# ADC.net
KiCad netlist of a schematic drawn in Altium Designer
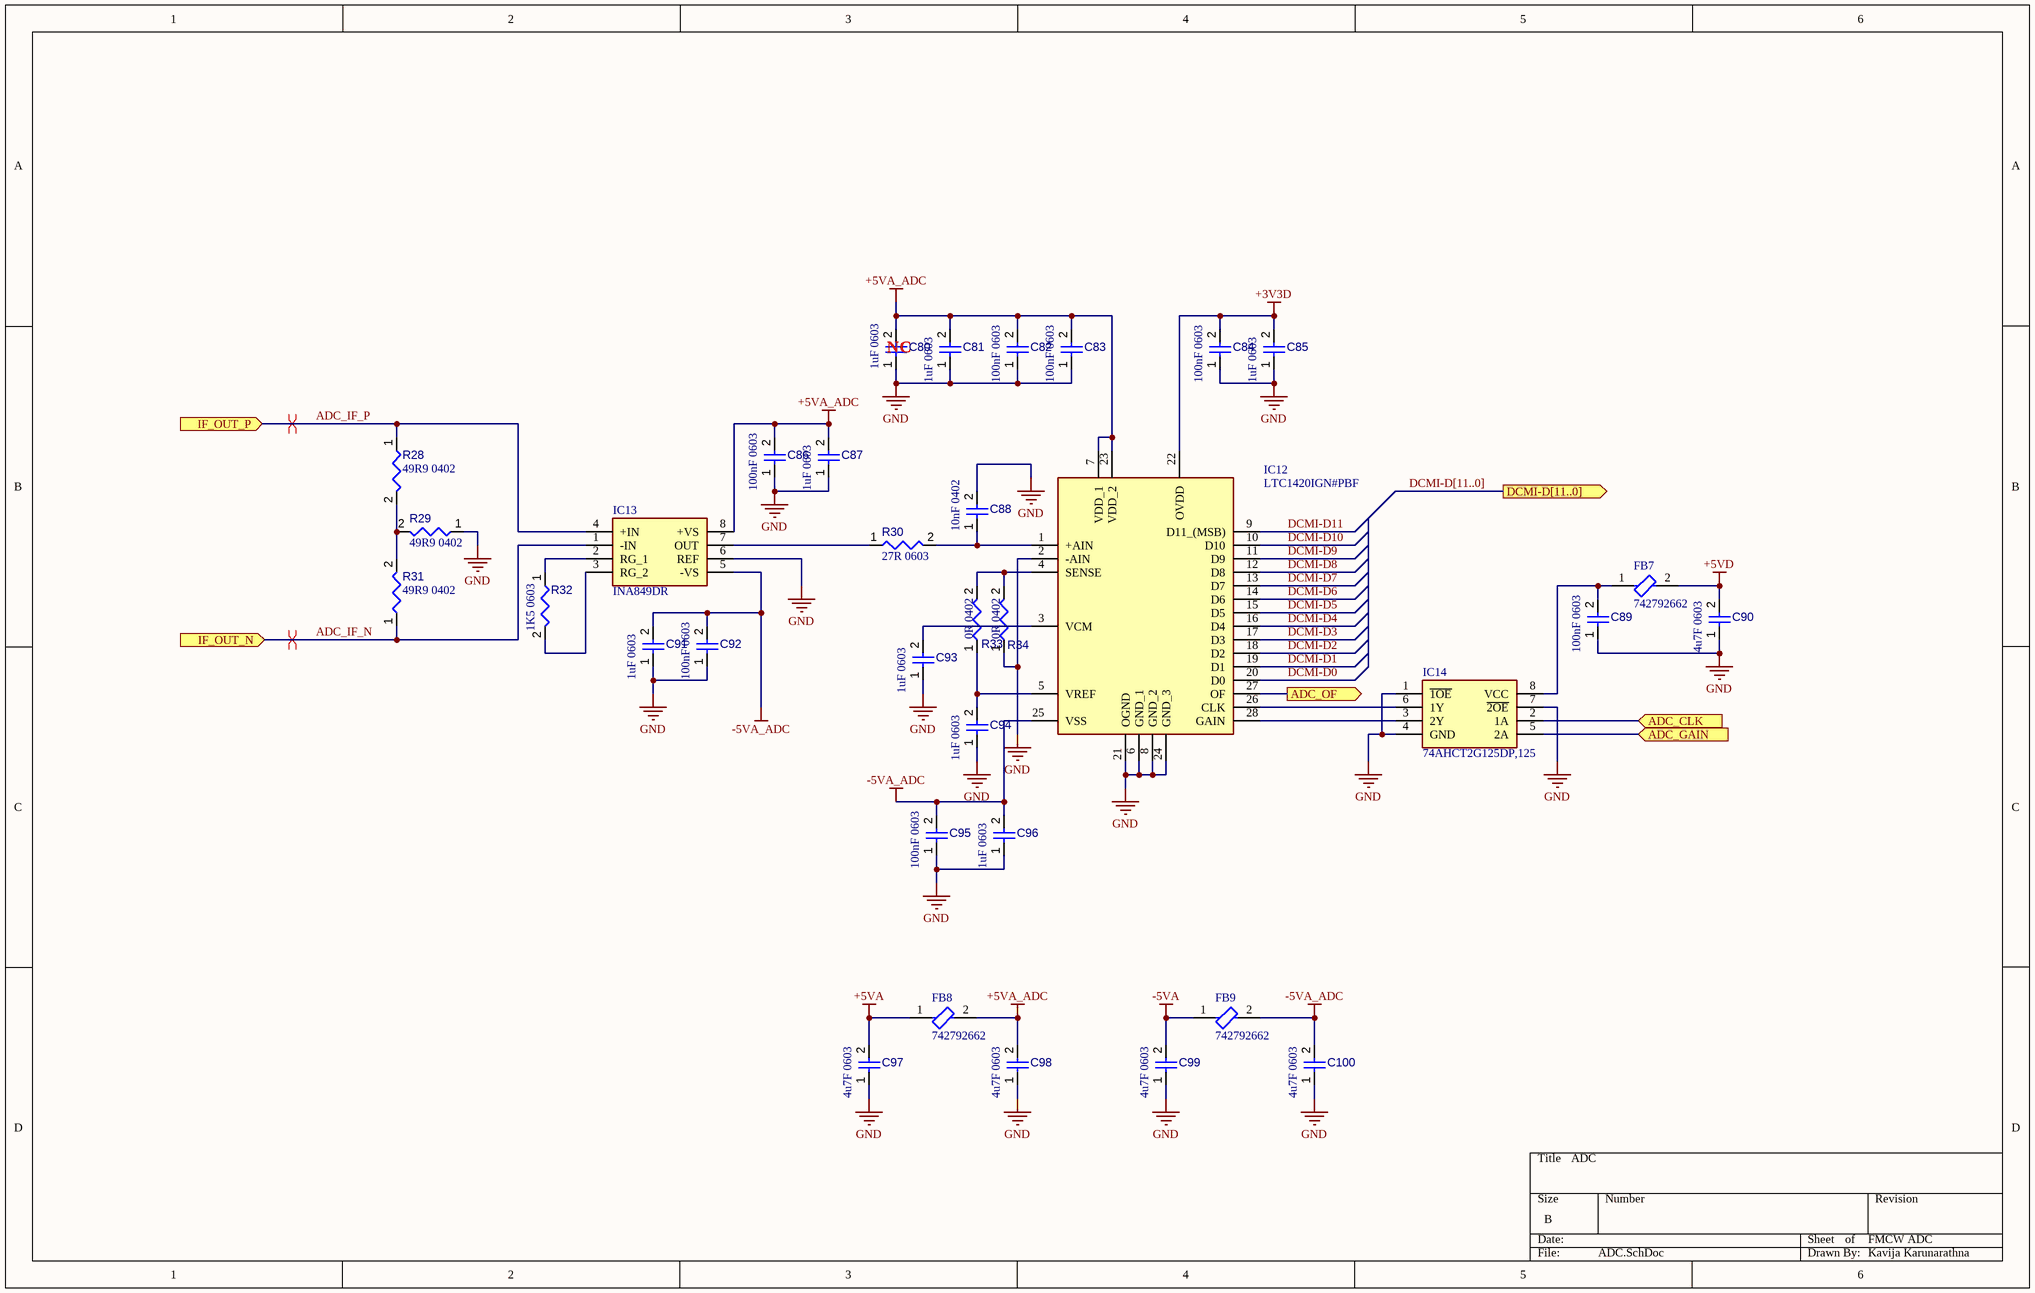
[diagram p0: ADC.SchDoc]

(export (version "E")
  (design (tool "Eeschema 10.0.6"))
  (components
    (comp (ref "C80")
      (value "1uF 0603")
      (footprint "CAPC0603(1608)100_L")
      (description "Chip Capacitor, 1µF +/-0.1%, 25V, 0603, Thickness 1 mm")
      (fields (field (name "TOLERANCE") "20%") (field (name "MANUFACTURER PART NO") "0603YC105KAZ2A"))
      (libsource (lib "Kavija Karunarathna") (part "CAP-NP-2"))
    )
    (comp (ref "C81")
      (value "1uF 0603")
      (footprint "CAPC0603(1608)100_L")
      (description "Chip Capacitor, 1µF +/-0.1%, 25V, 0603, Thickness 1 mm")
      (fields (field (name "TOLERANCE") "20%") (field (name "MANUFACTURER PART NO") "0603YC105KAZ2A"))
      (libsource (lib "Kavija Karunarathna") (part "CAP-NP-2"))
    )
    (comp (ref "C82")
      (value "100nF 0603")
      (footprint "CAPC0603(1608)100_L")
      (description "Chip Capacitor, 1µF +/-0.1%, 25V, 0603, Thickness 1 mm")
      (fields (field (name "TOLERANCE") "20%") (field (name "MANUFACTURER PART NO") "0603X104K250CT"))
      (libsource (lib "Kavija Karunarathna") (part "CAP-NP-2"))
    )
    (comp (ref "C83")
      (value "100nF 0603")
      (footprint "CAPC0603(1608)100_L")
      (description "Chip Capacitor, 1µF +/-0.1%, 25V, 0603, Thickness 1 mm")
      (fields (field (name "TOLERANCE") "20%") (field (name "MANUFACTURER PART NO") "0603X104K250CT"))
      (libsource (lib "Kavija Karunarathna") (part "CAP-NP-2"))
    )
    (comp (ref "C84")
      (value "100nF 0603")
      (footprint "CAPC0603(1608)100_L")
      (description "Chip Capacitor, 1µF +/-0.1%, 25V, 0603, Thickness 1 mm")
      (fields (field (name "TOLERANCE") "20%") (field (name "MANUFACTURER PART NO") "0603X104K250CT"))
      (libsource (lib "Kavija Karunarathna") (part "CAP-NP-2"))
    )
    (comp (ref "C85")
      (value "1uF 0603")
      (footprint "CAPC0603(1608)100_L")
      (description "Chip Capacitor, 1µF +/-0.1%, 25V, 0603, Thickness 1 mm")
      (fields (field (name "TOLERANCE") "20%") (field (name "MANUFACTURER PART NO") "0603YC105KAZ2A"))
      (libsource (lib "Kavija Karunarathna") (part "CAP-NP-2"))
    )
    (comp (ref "C86")
      (value "100nF 0603")
      (footprint "CAPC0603(1608)100_L")
      (description "Chip Capacitor, 1µF +/-0.1%, 25V, 0603, Thickness 1 mm")
      (fields (field (name "TOLERANCE") "20%") (field (name "MANUFACTURER PART NO") "0603X104K250CT"))
      (libsource (lib "Kavija Karunarathna") (part "CAP-NP-2"))
    )
    (comp (ref "C87")
      (value "1uF 0603")
      (footprint "CAPC0603(1608)100_L")
      (description "Chip Capacitor, 1µF +/-0.1%, 25V, 0603, Thickness 1 mm")
      (fields (field (name "TOLERANCE") "20%") (field (name "MANUFACTURER PART NO") "0603YC105KAZ2A"))
      (libsource (lib "Kavija Karunarathna") (part "CAP-NP-2"))
    )
    (comp (ref "C88")
      (value "10nF 0402")
      (footprint "CAPC0402(1005)60_L")
      (description "Multilayer Ceramic Capacitors MLCC - SMD/SMT 50 V 10 pF C0G 0402 1%")
      (fields (field (name "TOLERANCE") "20%") (field (name "MANUFACTURER PART NO") "VJ0402Y103JXJAC"))
      (libsource (lib "Kavija Karunarathna") (part "CAP-NP-2"))
    )
    (comp (ref "C89")
      (value "100nF 0603")
      (footprint "CAPC0603(1608)100_L")
      (description "Chip Capacitor, 1µF +/-0.1%, 25V, 0603, Thickness 1 mm")
      (fields (field (name "TOLERANCE") "20%") (field (name "MANUFACTURER PART NO") "0603X104K250CT"))
      (libsource (lib "Kavija Karunarathna") (part "CAP-NP-2"))
    )
    (comp (ref "C90")
      (value "4u7F 0603")
      (footprint "CAPC0603(1608)100_L")
      (description "Chip Capacitor, 1µF +/-0.1%, 25V, 0603, Thickness 1 mm")
      (fields (field (name "TOLERANCE") "20%") (field (name "MANUFACTURER PART NO") "06033D475KAT2A"))
      (libsource (lib "Kavija Karunarathna") (part "CAP-NP-2"))
    )
    (comp (ref "C91")
      (value "1uF 0603")
      (footprint "CAPC0603(1608)100_L")
      (description "Chip Capacitor, 1µF +/-0.1%, 25V, 0603, Thickness 1 mm")
      (fields (field (name "TOLERANCE") "20%") (field (name "MANUFACTURER PART NO") "0603YC105KAZ2A"))
      (libsource (lib "Kavija Karunarathna") (part "CAP-NP-2"))
    )
    (comp (ref "C92")
      (value "100nF 0603")
      (footprint "CAPC0603(1608)100_L")
      (description "Chip Capacitor, 1µF +/-0.1%, 25V, 0603, Thickness 1 mm")
      (fields (field (name "TOLERANCE") "20%") (field (name "MANUFACTURER PART NO") "0603X104K250CT"))
      (libsource (lib "Kavija Karunarathna") (part "CAP-NP-2"))
    )
    (comp (ref "C93")
      (value "1uF 0603")
      (footprint "CAPC0603(1608)100_L")
      (description "Chip Capacitor, 1µF +/-0.1%, 25V, 0603, Thickness 1 mm")
      (fields (field (name "TOLERANCE") "20%") (field (name "MANUFACTURER PART NO") "0603YC105KAZ2A"))
      (libsource (lib "Kavija Karunarathna") (part "CAP-NP-2"))
    )
    (comp (ref "C94")
      (value "1uF 0603")
      (footprint "CAPC0603(1608)100_L")
      (description "Chip Capacitor, 1µF +/-0.1%, 25V, 0603, Thickness 1 mm")
      (fields (field (name "TOLERANCE") "20%") (field (name "MANUFACTURER PART NO") "0603YC105KAZ2A"))
      (libsource (lib "Kavija Karunarathna") (part "CAP-NP-2"))
    )
    (comp (ref "C95")
      (value "100nF 0603")
      (footprint "CAPC0603(1608)100_L")
      (description "Chip Capacitor, 1µF +/-0.1%, 25V, 0603, Thickness 1 mm")
      (fields (field (name "TOLERANCE") "20%") (field (name "MANUFACTURER PART NO") "0603X104K250CT"))
      (libsource (lib "Kavija Karunarathna") (part "CAP-NP-2"))
    )
    (comp (ref "C96")
      (value "1uF 0603")
      (footprint "CAPC0603(1608)100_L")
      (description "Chip Capacitor, 1µF +/-0.1%, 25V, 0603, Thickness 1 mm")
      (fields (field (name "TOLERANCE") "20%") (field (name "MANUFACTURER PART NO") "0603YC105KAZ2A"))
      (libsource (lib "Kavija Karunarathna") (part "CAP-NP-2"))
    )
    (comp (ref "C97")
      (value "4u7F 0603")
      (footprint "CAPC0603(1608)100_L")
      (description "Chip Capacitor, 1µF +/-0.1%, 25V, 0603, Thickness 1 mm")
      (fields (field (name "TOLERANCE") "20%") (field (name "MANUFACTURER PART NO") "06033D475KAT2A"))
      (libsource (lib "Kavija Karunarathna") (part "CAP-NP-2"))
    )
    (comp (ref "C98")
      (value "4u7F 0603")
      (footprint "CAPC0603(1608)100_L")
      (description "Chip Capacitor, 1µF +/-0.1%, 25V, 0603, Thickness 1 mm")
      (fields (field (name "TOLERANCE") "20%") (field (name "MANUFACTURER PART NO") "06033D475KAT2A"))
      (libsource (lib "Kavija Karunarathna") (part "CAP-NP-2"))
    )
    (comp (ref "C99")
      (value "4u7F 0603")
      (footprint "CAPC0603(1608)100_L")
      (description "Chip Capacitor, 1µF +/-0.1%, 25V, 0603, Thickness 1 mm")
      (fields (field (name "TOLERANCE") "20%") (field (name "MANUFACTURER PART NO") "06033D475KAT2A"))
      (libsource (lib "Kavija Karunarathna") (part "CAP-NP-2"))
    )
    (comp (ref "C100")
      (value "4u7F 0603")
      (footprint "CAPC0603(1608)100_L")
      (description "Chip Capacitor, 1µF +/-0.1%, 25V, 0603, Thickness 1 mm")
      (fields (field (name "TOLERANCE") "20%") (field (name "MANUFACTURER PART NO") "06033D475KAT2A"))
      (libsource (lib "Kavija Karunarathna") (part "CAP-NP-2"))
    )
    (comp (ref "FB7")
      (value "742792662")
      (footprint "FB-0603")
      (description "FERRITE BEAD 0603")
      (fields (field (name "MOUSER PART NO") "710-742792662"))
      (libsource (lib "SchLib") (part "742792662-FB"))
    )
    (comp (ref "FB8")
      (value "742792662")
      (footprint "FB-0603")
      (description "FERRITE BEAD 0603")
      (fields (field (name "MOUSER PART NO") "710-742792662"))
      (libsource (lib "SchLib") (part "742792662-FB"))
    )
    (comp (ref "FB9")
      (value "742792662")
      (footprint "FB-0603")
      (description "FERRITE BEAD 0603")
      (fields (field (name "MOUSER PART NO") "710-742792662"))
      (libsource (lib "SchLib") (part "742792662-FB"))
    )
    (comp (ref "IC12")
      (value "LTC1420IGN#PBF")
      (footprint "SOP64P601X175-28N")
      (description "Integrated Circuit")
      (fields (field (name "MOUSER PART NO") "584-LTC1420IGN#PBF"))
      (libsource (lib "SchLib") (part "LTC1420IGN#PBF"))
    )
    (comp (ref "IC13")
      (value "INA849DR")
      (footprint "SOIC127P600X175-8N")
      (description "Integrated Circuit")
      (fields (field (name "MOUSER PART NO") "595-INA849DR"))
      (libsource (lib "SchLib") (part "INA849DR"))
    )
    (comp (ref "IC14")
      (value "74AHCT2G125DP,125")
      (footprint "SOP65P400X110-8N")
      (description "Integrated Circuit")
      (fields (field (name "MOUSER PART NO") "771-AHCT2G125DP125"))
      (libsource (lib "SchLib") (part "74AHCT2G125DP,125"))
    )
    (comp (ref "R28")
      (value "49R9 0402")
      (footprint "RESC0402(1005)_L")
      (description "Thin Film Resistors - SMD 49.9 OHM .1% 50PPM 1/16W")
      (fields (field (name "TOLERANCE") "1%") (field (name "POWER") "100mW"))
      (libsource (lib "Kavija Karunarathna") (part "383KR2F"))
    )
    (comp (ref "R29")
      (value "49R9 0402")
      (footprint "RESC0402(1005)_L")
      (description "Thin Film Resistors - SMD 49.9 OHM .1% 50PPM 1/16W")
      (fields (field (name "TOLERANCE") "1%") (field (name "POWER") "100mW"))
      (libsource (lib "Kavija Karunarathna") (part "383KR2F"))
    )
    (comp (ref "R30")
      (value "27R 0603")
      (footprint "RESC0603(1608)_L")
      (description "Thick Film Resistors - SMD General Purpose Chip Resistor 0603, 200Ohms, 1%, 1/10W")
      (fields (field (name "POWER") "100mW") (field (name "TOLERANCE") "5%"))
      (libsource (lib "Kavija Karunarathna") (part "120R3J"))
    )
    (comp (ref "R31")
      (value "49R9 0402")
      (footprint "RESC0402(1005)_L")
      (description "Thin Film Resistors - SMD 49.9 OHM .1% 50PPM 1/16W")
      (fields (field (name "TOLERANCE") "1%") (field (name "POWER") "100mW"))
      (libsource (lib "Kavija Karunarathna") (part "383KR2F"))
    )
    (comp (ref "R32")
      (value "1K5 0603")
      (footprint "RESC0603(1608)_L")
      (description "Thick Film Resistors - SMD WRIS-RSKS 100 Ohms 1 % 0.1 W 0603 AEC-Q200")
      (fields (field (name "POWER") "100mW") (field (name "TOLERANCE") "5%"))
      (libsource (lib "Kavija Karunarathna") (part "120R3J"))
    )
    (comp (ref "R33")
      (value "0R 0402")
      (footprint "RESC0402(1005)_L")
      (description "Thick Film Resistors - SMD 0 Ohms 1/16 W 50 V 5 % 0402 - 55 C / + 155 C AEC-Q200")
      (fields (field (name "TOLERANCE") "1%") (field (name "POWER") "100mW"))
      (libsource (lib "Kavija Karunarathna") (part "383KR2F"))
    )
    (comp (ref "R34")
      (value "0R 0402")
      (footprint "RESC0402(1005)_L")
      (description "Thick Film Resistors - SMD 0 Ohms 1/16 W 50 V 5 % 0402 - 55 C / + 155 C AEC-Q200")
      (fields (field (name "TOLERANCE") "1%") (field (name "POWER") "100mW"))
      (libsource (lib "Kavija Karunarathna") (part "383KR2F"))
    )
  )
  (nets
    (net (code "1") (name "+3V3D") (class "Default")
      (node (ref "C84") (pin "2") (pinfunction "2_2") (pintype "passive"))
      (node (ref "C85") (pin "2") (pinfunction "2_2") (pintype "passive"))
      (node (ref "IC12") (pin "22") (pinfunction "OVDD_22") (pintype "passive"))
    )
    (net (code "2") (name "+5VA") (class "Default")
      (node (ref "C97") (pin "2") (pinfunction "2_2") (pintype "passive"))
      (node (ref "FB8") (pin "1") (pinfunction "1_1") (pintype "passive"))
    )
    (net (code "3") (name "+5VA_ADC") (class "Default")
      (node (ref "C80") (pin "2") (pinfunction "2_2") (pintype "passive"))
      (node (ref "C81") (pin "2") (pinfunction "2_2") (pintype "passive"))
      (node (ref "C82") (pin "2") (pinfunction "2_2") (pintype "passive"))
      (node (ref "C83") (pin "2") (pinfunction "2_2") (pintype "passive"))
      (node (ref "C86") (pin "2") (pinfunction "2_2") (pintype "passive"))
      (node (ref "C87") (pin "2") (pinfunction "2_2") (pintype "passive"))
      (node (ref "C98") (pin "2") (pinfunction "2_2") (pintype "passive"))
      (node (ref "FB8") (pin "2") (pinfunction "2_2") (pintype "passive"))
      (node (ref "IC12") (pin "23") (pinfunction "VDD_2_23") (pintype "passive"))
      (node (ref "IC12") (pin "7") (pinfunction "VDD_1_7") (pintype "passive"))
      (node (ref "IC13") (pin "8") (pinfunction "+VS_8") (pintype "passive"))
    )
    (net (code "4") (name "+5VD") (class "Default")
      (node (ref "C90") (pin "2") (pinfunction "2_2") (pintype "passive"))
      (node (ref "FB7") (pin "2") (pinfunction "2_2") (pintype "passive"))
    )
    (net (code "5") (name "-5VA") (class "Default")
      (node (ref "C99") (pin "2") (pinfunction "2_2") (pintype "passive"))
      (node (ref "FB9") (pin "1") (pinfunction "1_1") (pintype "passive"))
    )
    (net (code "6") (name "-5VA_ADC") (class "Default")
      (node (ref "C100") (pin "2") (pinfunction "2_2") (pintype "passive"))
      (node (ref "C91") (pin "2") (pinfunction "2_2") (pintype "passive"))
      (node (ref "C92") (pin "2") (pinfunction "2_2") (pintype "passive"))
      (node (ref "C95") (pin "2") (pinfunction "2_2") (pintype "passive"))
      (node (ref "C96") (pin "2") (pinfunction "2_2") (pintype "passive"))
      (node (ref "FB9") (pin "2") (pinfunction "2_2") (pintype "passive"))
      (node (ref "IC12") (pin "25") (pinfunction "VSS_25") (pintype "passive"))
      (node (ref "IC13") (pin "5") (pinfunction "-VS_5") (pintype "passive"))
    )
    (net (code "7") (name "/ADC_CLK") (class "Default")
      (node (ref "IC14") (pin "2") (pinfunction "1A_2") (pintype "passive"))
    )
    (net (code "8") (name "/ADC_GAIN") (class "Default")
      (node (ref "IC14") (pin "5") (pinfunction "2A_5") (pintype "passive"))
    )
    (net (code "9") (name "/ADC_IF_N") (class "Default")
      (node (ref "IC13") (pin "1") (pinfunction "-IN_1") (pintype "passive"))
      (node (ref "R31") (pin "1") (pinfunction "1_1") (pintype "passive"))
    )
    (net (code "10") (name "/ADC_IF_P") (class "Default")
      (node (ref "IC13") (pin "4") (pinfunction "+IN_4") (pintype "passive"))
      (node (ref "R28") (pin "1") (pinfunction "1_1") (pintype "passive"))
    )
    (net (code "11") (name "/ADC_OF") (class "Default")
      (node (ref "IC12") (pin "27") (pinfunction "OF_27") (pintype "passive"))
    )
    (net (code "12") (name "/DCMI-D0") (class "Default")
      (node (ref "IC12") (pin "20") (pinfunction "D0_20") (pintype "passive"))
    )
    (net (code "13") (name "/DCMI-D1") (class "Default")
      (node (ref "IC12") (pin "19") (pinfunction "D1_19") (pintype "passive"))
    )
    (net (code "14") (name "/DCMI-D2") (class "Default")
      (node (ref "IC12") (pin "18") (pinfunction "D2_18") (pintype "passive"))
    )
    (net (code "15") (name "/DCMI-D3") (class "Default")
      (node (ref "IC12") (pin "17") (pinfunction "D3_17") (pintype "passive"))
    )
    (net (code "16") (name "/DCMI-D4") (class "Default")
      (node (ref "IC12") (pin "16") (pinfunction "D4_16") (pintype "passive"))
    )
    (net (code "17") (name "/DCMI-D5") (class "Default")
      (node (ref "IC12") (pin "15") (pinfunction "D5_15") (pintype "passive"))
    )
    (net (code "18") (name "/DCMI-D6") (class "Default")
      (node (ref "IC12") (pin "14") (pinfunction "D6_14") (pintype "passive"))
    )
    (net (code "19") (name "/DCMI-D7") (class "Default")
      (node (ref "IC12") (pin "13") (pinfunction "D7_13") (pintype "passive"))
    )
    (net (code "20") (name "/DCMI-D8") (class "Default")
      (node (ref "IC12") (pin "12") (pinfunction "D8_12") (pintype "passive"))
    )
    (net (code "21") (name "/DCMI-D9") (class "Default")
      (node (ref "IC12") (pin "11") (pinfunction "D9_11") (pintype "passive"))
    )
    (net (code "22") (name "/DCMI-D10") (class "Default")
      (node (ref "IC12") (pin "10") (pinfunction "D10_10") (pintype "passive"))
    )
    (net (code "23") (name "/DCMI-D11") (class "Default")
      (node (ref "IC12") (pin "9") (pinfunction "D11_(MSB)_9") (pintype "passive"))
    )
    (net (code "25") (name "GND") (class "Default")
      (node (ref "C100") (pin "1") (pinfunction "1_1") (pintype "passive"))
      (node (ref "C80") (pin "1") (pinfunction "1_1") (pintype "passive"))
      (node (ref "C81") (pin "1") (pinfunction "1_1") (pintype "passive"))
      (node (ref "C82") (pin "1") (pinfunction "1_1") (pintype "passive"))
      (node (ref "C83") (pin "1") (pinfunction "1_1") (pintype "passive"))
      (node (ref "C84") (pin "1") (pinfunction "1_1") (pintype "passive"))
      (node (ref "C85") (pin "1") (pinfunction "1_1") (pintype "passive"))
      (node (ref "C86") (pin "1") (pinfunction "1_1") (pintype "passive"))
      (node (ref "C87") (pin "1") (pinfunction "1_1") (pintype "passive"))
      (node (ref "C88") (pin "2") (pinfunction "2_2") (pintype "passive"))
      (node (ref "C89") (pin "1") (pinfunction "1_1") (pintype "passive"))
      (node (ref "C90") (pin "1") (pinfunction "1_1") (pintype "passive"))
      (node (ref "C91") (pin "1") (pinfunction "1_1") (pintype "passive"))
      (node (ref "C92") (pin "1") (pinfunction "1_1") (pintype "passive"))
      (node (ref "C93") (pin "1") (pinfunction "1_1") (pintype "passive"))
      (node (ref "C94") (pin "1") (pinfunction "1_1") (pintype "passive"))
      (node (ref "C95") (pin "1") (pinfunction "1_1") (pintype "passive"))
      (node (ref "C96") (pin "1") (pinfunction "1_1") (pintype "passive"))
      (node (ref "C97") (pin "1") (pinfunction "1_1") (pintype "passive"))
      (node (ref "C98") (pin "1") (pinfunction "1_1") (pintype "passive"))
      (node (ref "C99") (pin "1") (pinfunction "1_1") (pintype "passive"))
      (node (ref "IC12") (pin "2") (pinfunction "-AIN_2") (pintype "passive"))
      (node (ref "IC12") (pin "21") (pinfunction "OGND_21") (pintype "passive"))
      (node (ref "IC12") (pin "24") (pinfunction "GND_3_24") (pintype "passive"))
      (node (ref "IC12") (pin "6") (pinfunction "GND_1_6") (pintype "passive"))
      (node (ref "IC12") (pin "8") (pinfunction "GND_2_8") (pintype "passive"))
      (node (ref "IC13") (pin "6") (pinfunction "REF_6") (pintype "passive"))
      (node (ref "IC14") (pin "1") (pinfunction "~{1OE}_1") (pintype "passive"))
      (node (ref "IC14") (pin "4") (pinfunction "GND_4") (pintype "passive"))
      (node (ref "IC14") (pin "7") (pinfunction "~{2OE}_7") (pintype "passive"))
      (node (ref "R29") (pin "1") (pinfunction "1_1") (pintype "passive"))
      (node (ref "R34") (pin "1") (pinfunction "1_1") (pintype "passive"))
    )
    (net (code "26") (name "Net-(IC12-+AIN)") (class "Default")
      (node (ref "C88") (pin "1") (pinfunction "1_1") (pintype "passive"))
      (node (ref "IC12") (pin "1") (pinfunction "+AIN_1") (pintype "passive"))
      (node (ref "R30") (pin "2") (pinfunction "2_2") (pintype "passive"))
    )
    (net (code "27") (name "Net-(IC12-CLK)") (class "Default")
      (node (ref "IC12") (pin "26") (pinfunction "CLK_26") (pintype "passive"))
      (node (ref "IC14") (pin "6") (pinfunction "1Y_6") (pintype "passive"))
    )
    (net (code "28") (name "Net-(IC12-GAIN)") (class "Default")
      (node (ref "IC12") (pin "28") (pinfunction "GAIN_28") (pintype "passive"))
      (node (ref "IC14") (pin "3") (pinfunction "2Y_3") (pintype "passive"))
    )
    (net (code "29") (name "Net-(IC12-SENSE)") (class "Default")
      (node (ref "IC12") (pin "4") (pinfunction "SENSE_4") (pintype "passive"))
      (node (ref "R33") (pin "2") (pinfunction "2_2") (pintype "passive"))
      (node (ref "R34") (pin "2") (pinfunction "2_2") (pintype "passive"))
    )
    (net (code "30") (name "Net-(IC12-VCM)") (class "Default")
      (node (ref "C93") (pin "2") (pinfunction "2_2") (pintype "passive"))
      (node (ref "IC12") (pin "3") (pinfunction "VCM_3") (pintype "passive"))
    )
    (net (code "31") (name "Net-(IC12-VREF)") (class "Default")
      (node (ref "C94") (pin "2") (pinfunction "2_2") (pintype "passive"))
      (node (ref "IC12") (pin "5") (pinfunction "VREF_5") (pintype "passive"))
      (node (ref "R33") (pin "1") (pinfunction "1_1") (pintype "passive"))
    )
    (net (code "32") (name "Net-(IC13-OUT)") (class "Default")
      (node (ref "IC13") (pin "7") (pinfunction "OUT_7") (pintype "passive"))
      (node (ref "R30") (pin "1") (pinfunction "1_1") (pintype "passive"))
    )
    (net (code "33") (name "Net-(IC13-RG_1)") (class "Default")
      (node (ref "IC13") (pin "2") (pinfunction "RG_1_2") (pintype "passive"))
      (node (ref "R32") (pin "1") (pinfunction "1_1") (pintype "passive"))
    )
    (net (code "34") (name "Net-(IC13-RG_2)") (class "Default")
      (node (ref "IC13") (pin "3") (pinfunction "RG_2_3") (pintype "passive"))
      (node (ref "R32") (pin "2") (pinfunction "2_2") (pintype "passive"))
    )
    (net (code "35") (name "Net-(IC14-VCC)") (class "Default")
      (node (ref "C89") (pin "2") (pinfunction "2_2") (pintype "passive"))
      (node (ref "FB7") (pin "1") (pinfunction "1_1") (pintype "passive"))
      (node (ref "IC14") (pin "8") (pinfunction "VCC_8") (pintype "passive"))
    )
    (net (code "36") (name "Net-(R28-Pad2)") (class "Default")
      (node (ref "R28") (pin "2") (pinfunction "2_2") (pintype "passive"))
      (node (ref "R29") (pin "2") (pinfunction "2_2") (pintype "passive"))
      (node (ref "R31") (pin "2") (pinfunction "2_2") (pintype "passive"))
    )
  )
)
